# LED.net
KiCad netlist of a schematic drawn in EasyEDA Pro
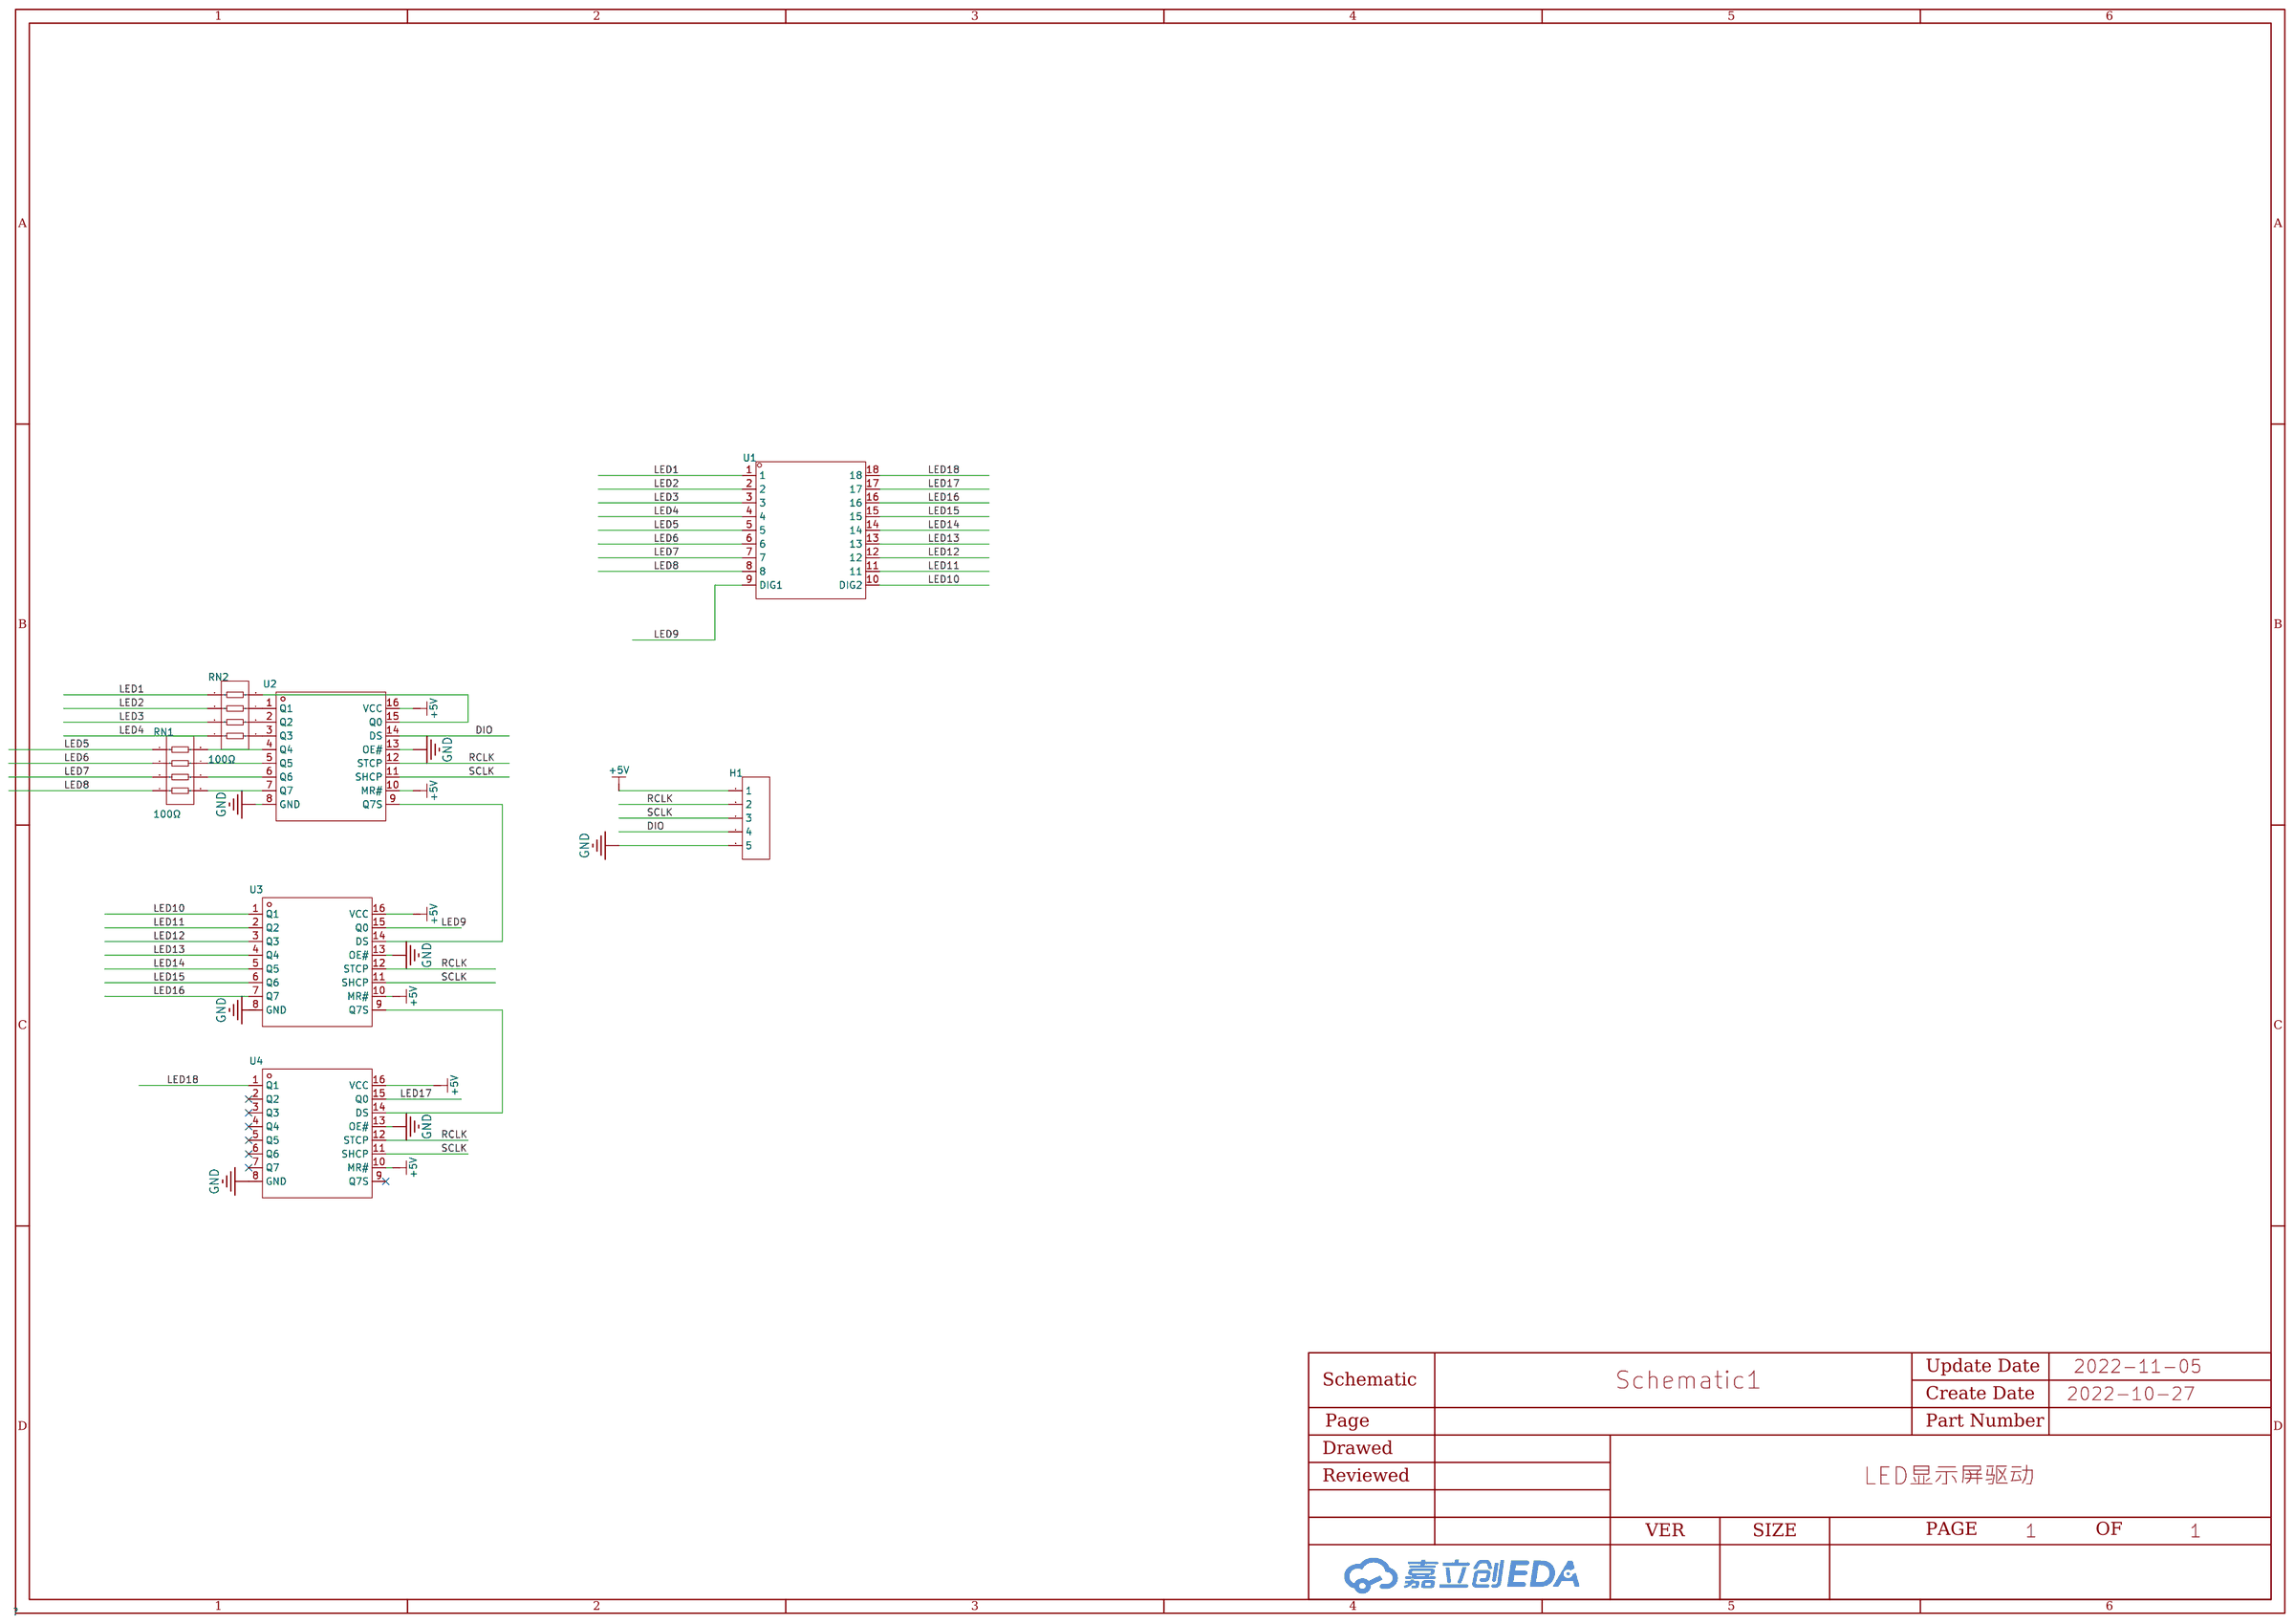
[diagram p0: schematic sheet]

(export (version "E")
  (design (tool "Eeschema 10.0.6"))
  (components
    (comp (ref "H1")
      (value "2.54-1*5P母")
      (footprint "easyedapro:HDR-TH_5P-P2.54-V-F")
      (description "间距:2.54mm;总孔位数:5;排数:1;插孔结构:1x5P;行距:-;安装类型:直插;塑高:-;触头材质:-;触头镀层:-;")
      (fields (field (name "Manufacturer") "BOOMELE(博穆精密)"))
      (libsource (lib "easyedapro") (part "Header-Female-2.54_1x5"))
    )
    (comp (ref "RN1")
      (value "100Ω")
      (footprint "easyedapro:RES-ARRAY-SMD_0603-8P-L3.2-W1.6")
      (description "阻值:910kΩ;精度:±5%;单个元件功率:100mW;温度系数:±200ppm/°C;电阻器数:4;引脚数:8;")
      (fields
        (field (name "Manufacturer Part") "4D03WAJ0914T5E")
        (field (name "Manufacturer") "UNI-ROYAL(厚声)")
      )
      (libsource (lib "easyedapro") (part "4D03WAJ0914T5E"))
    )
    (comp (ref "RN2")
      (value "100Ω")
      (footprint "easyedapro:RES-ARRAY-SMD_0603-8P-L3.2-W1.6")
      (description "阻值:910kΩ;精度:±5%;单个元件功率:100mW;温度系数:±200ppm/°C;电阻器数:4;引脚数:8;")
      (fields
        (field (name "Manufacturer Part") "4D03WAJ0914T5E")
        (field (name "Manufacturer") "UNI-ROYAL(厚声)")
      )
      (libsource (lib "easyedapro") (part "4D03WAJ0914T5E"))
    )
    (comp (ref "U1")
      (value "TOD-6281AMA-B4")
      (footprint "easyedapro:LED-SEG-TH_18P-L94.0-W36.0-P2.54-S30.5-BL")
      (description "数码管位数:-;数码管的显示尺寸:-;电路连线类型:-;照明颜色:-;主波长/色坐标:-;")
      (fields (field (name "Manufacturer") "OASIS(李洲)"))
      (libsource (lib "easyedapro") (part "TOD-6281AMA-B4"))
    )
    (comp (ref "U2")
      (value "74HC595S16-13")
      (footprint "easyedapro:SOIC-16_L10.8-W4.5-P1.27-LS6.8-BL")
      (description "逻辑电路的归属系列:74HC;逻辑类型:移位寄存器;输出类型:三态;功能:串行至并行, 串行;工作电压:2V~6V;")
      (fields (field (name "Manufacturer") "DIODES(美台)"))
      (libsource (lib "easyedapro") (part "74HC595S16-13"))
    )
    (comp (ref "U3")
      (value "74HC595S16-13")
      (footprint "easyedapro:SOIC-16_L10.8-W4.5-P1.27-LS6.8-BL")
      (description "逻辑电路的归属系列:74HC;逻辑类型:移位寄存器;输出类型:三态;功能:串行至并行, 串行;工作电压:2V~6V;")
      (fields (field (name "Manufacturer") "DIODES(美台)"))
      (libsource (lib "easyedapro") (part "74HC595S16-13"))
    )
    (comp (ref "U4")
      (value "74HC595S16-13")
      (footprint "easyedapro:SOIC-16_L10.8-W4.5-P1.27-LS6.8-BL")
      (description "逻辑电路的归属系列:74HC;逻辑类型:移位寄存器;输出类型:三态;功能:串行至并行, 串行;工作电压:2V~6V;")
      (fields (field (name "Manufacturer") "DIODES(美台)"))
      (libsource (lib "easyedapro") (part "74HC595S16-13"))
    )
  )
  (nets
    (net (code "1") (name "+5V") (class "Default")
      (node (ref "H1") (pin "1") (pinfunction "1_1") (pintype "input"))
      (node (ref "U2") (pin "10") (pinfunction "MR#_10") (pintype "input"))
      (node (ref "U2") (pin "16") (pinfunction "VCC_16") (pintype "input"))
      (node (ref "U3") (pin "10") (pinfunction "MR#_10") (pintype "input"))
      (node (ref "U3") (pin "16") (pinfunction "VCC_16") (pintype "input"))
      (node (ref "U4") (pin "10") (pinfunction "MR#_10") (pintype "input"))
      (node (ref "U4") (pin "16") (pinfunction "VCC_16") (pintype "input"))
    )
    (net (code "2") (name "/DIO") (class "Default")
      (node (ref "H1") (pin "4") (pinfunction "4_4") (pintype "input"))
      (node (ref "U2") (pin "14") (pinfunction "DS_14") (pintype "input"))
    )
    (net (code "3") (name "/LED1") (class "Default")
      (node (ref "RN2") (pin "1") (pinfunction "1_1") (pintype "input"))
      (node (ref "U1") (pin "1") (pinfunction "1_1") (pintype "input"))
    )
    (net (code "4") (name "/LED2") (class "Default")
      (node (ref "RN2") (pin "2") (pinfunction "2_2") (pintype "input"))
      (node (ref "U1") (pin "2") (pinfunction "2_2") (pintype "input"))
    )
    (net (code "5") (name "/LED3") (class "Default")
      (node (ref "RN2") (pin "3") (pinfunction "3_3") (pintype "input"))
      (node (ref "U1") (pin "3") (pinfunction "3_3") (pintype "input"))
    )
    (net (code "6") (name "/LED4") (class "Default")
      (node (ref "RN2") (pin "4") (pinfunction "4_4") (pintype "input"))
      (node (ref "U1") (pin "4") (pinfunction "4_4") (pintype "input"))
    )
    (net (code "7") (name "/LED5") (class "Default")
      (node (ref "RN1") (pin "1") (pinfunction "1_1") (pintype "input"))
      (node (ref "U1") (pin "5") (pinfunction "5_5") (pintype "input"))
    )
    (net (code "8") (name "/LED6") (class "Default")
      (node (ref "RN1") (pin "2") (pinfunction "2_2") (pintype "input"))
      (node (ref "U1") (pin "6") (pinfunction "6_6") (pintype "input"))
    )
    (net (code "9") (name "/LED7") (class "Default")
      (node (ref "RN1") (pin "3") (pinfunction "3_3") (pintype "input"))
      (node (ref "U1") (pin "7") (pinfunction "7_7") (pintype "input"))
    )
    (net (code "10") (name "/LED8") (class "Default")
      (node (ref "RN1") (pin "4") (pinfunction "4_4") (pintype "input"))
      (node (ref "U1") (pin "8") (pinfunction "8_8") (pintype "input"))
    )
    (net (code "11") (name "/LED9") (class "Default")
      (node (ref "U1") (pin "9") (pinfunction "DIG1_9") (pintype "input"))
      (node (ref "U3") (pin "15") (pinfunction "Q0_15") (pintype "input"))
    )
    (net (code "12") (name "/LED10") (class "Default")
      (node (ref "U1") (pin "10") (pinfunction "DIG2_10") (pintype "input"))
      (node (ref "U3") (pin "1") (pinfunction "Q1_1") (pintype "input"))
    )
    (net (code "13") (name "/LED11") (class "Default")
      (node (ref "U1") (pin "11") (pinfunction "11_11") (pintype "input"))
      (node (ref "U3") (pin "2") (pinfunction "Q2_2") (pintype "input"))
    )
    (net (code "14") (name "/LED12") (class "Default")
      (node (ref "U1") (pin "12") (pinfunction "12_12") (pintype "input"))
      (node (ref "U3") (pin "3") (pinfunction "Q3_3") (pintype "input"))
    )
    (net (code "15") (name "/LED13") (class "Default")
      (node (ref "U1") (pin "13") (pinfunction "13_13") (pintype "input"))
      (node (ref "U3") (pin "4") (pinfunction "Q4_4") (pintype "input"))
    )
    (net (code "16") (name "/LED14") (class "Default")
      (node (ref "U1") (pin "14") (pinfunction "14_14") (pintype "input"))
      (node (ref "U3") (pin "5") (pinfunction "Q5_5") (pintype "input"))
    )
    (net (code "17") (name "/LED15") (class "Default")
      (node (ref "U1") (pin "15") (pinfunction "15_15") (pintype "input"))
      (node (ref "U3") (pin "6") (pinfunction "Q6_6") (pintype "input"))
    )
    (net (code "18") (name "/LED16") (class "Default")
      (node (ref "U1") (pin "16") (pinfunction "16_16") (pintype "input"))
      (node (ref "U3") (pin "7") (pinfunction "Q7_7") (pintype "input"))
    )
    (net (code "19") (name "/LED17") (class "Default")
      (node (ref "U1") (pin "17") (pinfunction "17_17") (pintype "input"))
      (node (ref "U4") (pin "15") (pinfunction "Q0_15") (pintype "input"))
    )
    (net (code "20") (name "/LED18") (class "Default")
      (node (ref "U1") (pin "18") (pinfunction "18_18") (pintype "input"))
      (node (ref "U4") (pin "1") (pinfunction "Q1_1") (pintype "input"))
    )
    (net (code "21") (name "/RCLK") (class "Default")
      (node (ref "H1") (pin "2") (pinfunction "2_2") (pintype "input"))
      (node (ref "U2") (pin "12") (pinfunction "STCP_12") (pintype "input"))
      (node (ref "U3") (pin "12") (pinfunction "STCP_12") (pintype "input"))
      (node (ref "U4") (pin "12") (pinfunction "STCP_12") (pintype "input"))
    )
    (net (code "22") (name "/SCLK") (class "Default")
      (node (ref "H1") (pin "3") (pinfunction "3_3") (pintype "input"))
      (node (ref "U2") (pin "11") (pinfunction "SHCP_11") (pintype "input"))
      (node (ref "U3") (pin "11") (pinfunction "SHCP_11") (pintype "input"))
      (node (ref "U4") (pin "11") (pinfunction "SHCP_11") (pintype "input"))
    )
    (net (code "23") (name "GND") (class "Default")
      (node (ref "H1") (pin "5") (pinfunction "5_5") (pintype "input"))
      (node (ref "U2") (pin "13") (pinfunction "OE#_13") (pintype "input"))
      (node (ref "U2") (pin "8") (pinfunction "GND_8") (pintype "input"))
      (node (ref "U3") (pin "13") (pinfunction "OE#_13") (pintype "input"))
      (node (ref "U3") (pin "8") (pinfunction "GND_8") (pintype "input"))
      (node (ref "U4") (pin "13") (pinfunction "OE#_13") (pintype "input"))
      (node (ref "U4") (pin "8") (pinfunction "GND_8") (pintype "input"))
    )
    (net (code "24") (name "Net-(U2-Q0)") (class "Default")
      (node (ref "RN2") (pin "8") (pinfunction "8_8") (pintype "input"))
      (node (ref "U2") (pin "15") (pinfunction "Q0_15") (pintype "input"))
    )
    (net (code "25") (name "Net-(U2-Q1)") (class "Default")
      (node (ref "RN2") (pin "7") (pinfunction "7_7") (pintype "input"))
      (node (ref "U2") (pin "1") (pinfunction "Q1_1") (pintype "input"))
    )
    (net (code "26") (name "Net-(U2-Q2)") (class "Default")
      (node (ref "RN2") (pin "6") (pinfunction "6_6") (pintype "input"))
      (node (ref "U2") (pin "2") (pinfunction "Q2_2") (pintype "input"))
    )
    (net (code "27") (name "Net-(U2-Q3)") (class "Default")
      (node (ref "RN2") (pin "5") (pinfunction "5_5") (pintype "input"))
      (node (ref "U2") (pin "3") (pinfunction "Q3_3") (pintype "input"))
    )
    (net (code "28") (name "Net-(U2-Q4)") (class "Default")
      (node (ref "RN1") (pin "8") (pinfunction "8_8") (pintype "input"))
      (node (ref "U2") (pin "4") (pinfunction "Q4_4") (pintype "input"))
    )
    (net (code "29") (name "Net-(U2-Q5)") (class "Default")
      (node (ref "RN1") (pin "7") (pinfunction "7_7") (pintype "input"))
      (node (ref "U2") (pin "5") (pinfunction "Q5_5") (pintype "input"))
    )
    (net (code "30") (name "Net-(U2-Q6)") (class "Default")
      (node (ref "RN1") (pin "6") (pinfunction "6_6") (pintype "input"))
      (node (ref "U2") (pin "6") (pinfunction "Q6_6") (pintype "input"))
    )
    (net (code "31") (name "Net-(U2-Q7)") (class "Default")
      (node (ref "RN1") (pin "5") (pinfunction "5_5") (pintype "input"))
      (node (ref "U2") (pin "7") (pinfunction "Q7_7") (pintype "input"))
    )
    (net (code "32") (name "Net-(U2-Q7S)") (class "Default")
      (node (ref "U2") (pin "9") (pinfunction "Q7S_9") (pintype "input"))
      (node (ref "U3") (pin "14") (pinfunction "DS_14") (pintype "input"))
    )
    (net (code "33") (name "Net-(U3-Q7S)") (class "Default")
      (node (ref "U3") (pin "9") (pinfunction "Q7S_9") (pintype "input"))
      (node (ref "U4") (pin "14") (pinfunction "DS_14") (pintype "input"))
    )
    (net (code "34") (name "unconnected-(U4-Q2-Pad2)") (class "Default")
      (node (ref "U4") (pin "2") (pinfunction "Q2_2") (pintype "input+no_connect"))
    )
    (net (code "35") (name "unconnected-(U4-Q3-Pad3)") (class "Default")
      (node (ref "U4") (pin "3") (pinfunction "Q3_3") (pintype "input+no_connect"))
    )
    (net (code "36") (name "unconnected-(U4-Q4-Pad4)") (class "Default")
      (node (ref "U4") (pin "4") (pinfunction "Q4_4") (pintype "input+no_connect"))
    )
    (net (code "37") (name "unconnected-(U4-Q5-Pad5)") (class "Default")
      (node (ref "U4") (pin "5") (pinfunction "Q5_5") (pintype "input+no_connect"))
    )
    (net (code "38") (name "unconnected-(U4-Q6-Pad6)") (class "Default")
      (node (ref "U4") (pin "6") (pinfunction "Q6_6") (pintype "input+no_connect"))
    )
    (net (code "39") (name "unconnected-(U4-Q7-Pad7)") (class "Default")
      (node (ref "U4") (pin "7") (pinfunction "Q7_7") (pintype "input+no_connect"))
    )
    (net (code "40") (name "unconnected-(U4-Q7S-Pad9)") (class "Default")
      (node (ref "U4") (pin "9") (pinfunction "Q7S_9") (pintype "input+no_connect"))
    )
  )
)
